# CW308T_CC2538_UFO.net
KiCad netlist of a schematic drawn in Altium Designer
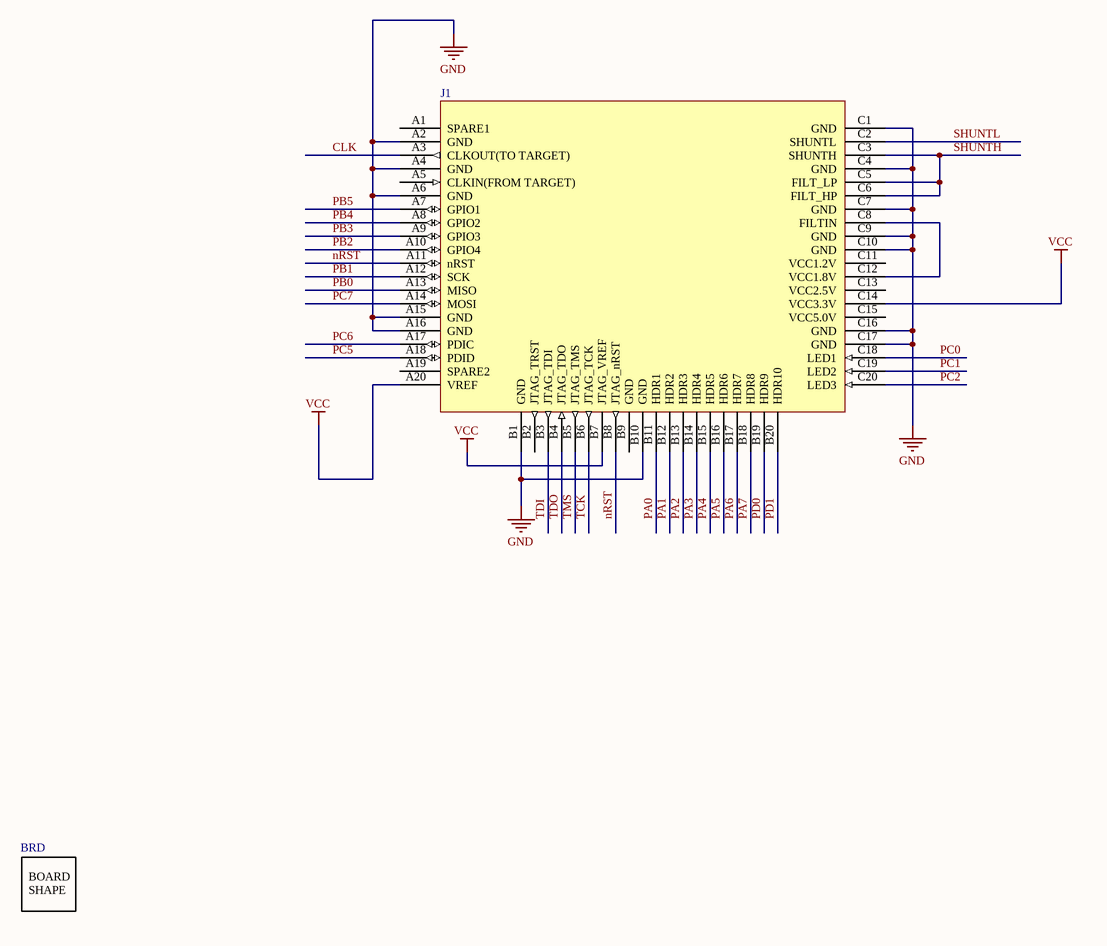
[diagram p0: CW308T_CC2538_UFO.SchDoc]

(export (version "E")
  (design (tool "Eeschema 10.0.6"))
  (components
    (comp (ref "BRD")
      (value "~")
      (footprint "CW308T_TBOARD_DEFSIZE")
      (description "308T Board Outline (Layer 1)")
      (fields (field (name "PART NUMBER") "CW308T_BRDSHAPE_DEFAULT"))
      (libsource (lib "NewAE_AltiumLib") (part "CW308_TBRDSIZE"))
    )
    (comp (ref "J1")
      (value "~")
      (footprint "CW308_TBOARD_CONN")
      (description "CW308 \"Standard\" Target Board Connector")
      (fields (field (name "PART NUMBER") "CW308_TBOARD"))
      (libsource (lib "NewAE_AltiumLib") (part "CW308_TBOARD"))
    )
  )
  (nets
    (net (code "1") (name "/CLK") (class "Default")
      (node (ref "J1") (pin "A3") (pinfunction "CLKOUT(TO_TARGET)_A3") (pintype "output"))
    )
    (net (code "2") (name "/PA0") (class "Default")
      (node (ref "J1") (pin "B11") (pinfunction "HDR1_B11") (pintype "passive"))
    )
    (net (code "3") (name "/PA1") (class "Default")
      (node (ref "J1") (pin "B12") (pinfunction "HDR2_B12") (pintype "passive"))
    )
    (net (code "4") (name "/PA2") (class "Default")
      (node (ref "J1") (pin "B13") (pinfunction "HDR3_B13") (pintype "passive"))
    )
    (net (code "5") (name "/PA3") (class "Default")
      (node (ref "J1") (pin "B14") (pinfunction "HDR4_B14") (pintype "passive"))
    )
    (net (code "6") (name "/PA4") (class "Default")
      (node (ref "J1") (pin "B15") (pinfunction "HDR5_B15") (pintype "passive"))
    )
    (net (code "7") (name "/PA5") (class "Default")
      (node (ref "J1") (pin "B16") (pinfunction "HDR6_B16") (pintype "passive"))
    )
    (net (code "8") (name "/PA6") (class "Default")
      (node (ref "J1") (pin "B17") (pinfunction "HDR7_B17") (pintype "passive"))
    )
    (net (code "9") (name "/PA7") (class "Default")
      (node (ref "J1") (pin "B18") (pinfunction "HDR8_B18") (pintype "passive"))
    )
    (net (code "10") (name "/PB0") (class "Default")
      (node (ref "J1") (pin "A13") (pinfunction "MISO_A13") (pintype "bidirectional"))
    )
    (net (code "11") (name "/PB1") (class "Default")
      (node (ref "J1") (pin "A12") (pinfunction "SCK_A12") (pintype "bidirectional"))
    )
    (net (code "12") (name "/PB2") (class "Default")
      (node (ref "J1") (pin "A10") (pinfunction "GPIO4_A10") (pintype "bidirectional"))
    )
    (net (code "13") (name "/PB3") (class "Default")
      (node (ref "J1") (pin "A9") (pinfunction "GPIO3_A9") (pintype "bidirectional"))
    )
    (net (code "14") (name "/PB4") (class "Default")
      (node (ref "J1") (pin "A8") (pinfunction "GPIO2_A8") (pintype "bidirectional"))
    )
    (net (code "15") (name "/PB5") (class "Default")
      (node (ref "J1") (pin "A7") (pinfunction "GPIO1_A7") (pintype "bidirectional"))
    )
    (net (code "16") (name "/PC0") (class "Default")
      (node (ref "J1") (pin "C18") (pinfunction "LED1_C18") (pintype "input"))
    )
    (net (code "17") (name "/PC1") (class "Default")
      (node (ref "J1") (pin "C19") (pinfunction "LED2_C19") (pintype "input"))
    )
    (net (code "18") (name "/PC2") (class "Default")
      (node (ref "J1") (pin "C20") (pinfunction "LED3_C20") (pintype "input"))
    )
    (net (code "19") (name "/PC5") (class "Default")
      (node (ref "J1") (pin "A18") (pinfunction "PDID_A18") (pintype "bidirectional"))
    )
    (net (code "20") (name "/PC6") (class "Default")
      (node (ref "J1") (pin "A17") (pinfunction "PDIC_A17") (pintype "bidirectional"))
    )
    (net (code "21") (name "/PC7") (class "Default")
      (node (ref "J1") (pin "A14") (pinfunction "MOSI_A14") (pintype "bidirectional"))
    )
    (net (code "22") (name "/PD0") (class "Default")
      (node (ref "J1") (pin "B19") (pinfunction "HDR9_B19") (pintype "passive"))
    )
    (net (code "23") (name "/PD1") (class "Default")
      (node (ref "J1") (pin "B20") (pinfunction "HDR10_B20") (pintype "passive"))
    )
    (net (code "24") (name "/SHUNTH") (class "Default")
      (node (ref "J1") (pin "C3") (pinfunction "SHUNTH_C3") (pintype "passive"))
      (node (ref "J1") (pin "C5") (pinfunction "FILT_LP_C5") (pintype "passive"))
      (node (ref "J1") (pin "C6") (pinfunction "FILT_HP_C6") (pintype "passive"))
    )
    (net (code "25") (name "/SHUNTL") (class "Default")
      (node (ref "J1") (pin "C2") (pinfunction "SHUNTL_C2") (pintype "passive"))
    )
    (net (code "26") (name "/TCK") (class "Default")
      (node (ref "J1") (pin "B6") (pinfunction "JTAG_TCK_B6") (pintype "output"))
    )
    (net (code "27") (name "/TDI") (class "Default")
      (node (ref "J1") (pin "B3") (pinfunction "JTAG_TDI_B3") (pintype "output"))
    )
    (net (code "28") (name "/TDO") (class "Default")
      (node (ref "J1") (pin "B4") (pinfunction "JTAG_TDO_B4") (pintype "input"))
    )
    (net (code "29") (name "/TMS") (class "Default")
      (node (ref "J1") (pin "B5") (pinfunction "JTAG_TMS_B5") (pintype "output"))
    )
    (net (code "30") (name "/nRST") (class "Default")
      (node (ref "J1") (pin "A11") (pinfunction "nRST_A11") (pintype "bidirectional"))
      (node (ref "J1") (pin "B8") (pinfunction "JTAG_nRST_B8") (pintype "output"))
    )
    (net (code "31") (name "GND") (class "Default")
      (node (ref "J1") (pin "A15") (pinfunction "GND_A15") (pintype "passive"))
      (node (ref "J1") (pin "A16") (pinfunction "GND_A16") (pintype "passive"))
      (node (ref "J1") (pin "A2") (pinfunction "GND_A2") (pintype "passive"))
      (node (ref "J1") (pin "A4") (pinfunction "GND_A4") (pintype "passive"))
      (node (ref "J1") (pin "A6") (pinfunction "GND_A6") (pintype "power_in"))
      (node (ref "J1") (pin "B1") (pinfunction "GND_B1") (pintype "passive"))
      (node (ref "J1") (pin "B10") (pinfunction "GND_B10") (pintype "passive"))
      (node (ref "J1") (pin "C1") (pinfunction "GND_C1") (pintype "power_in"))
      (node (ref "J1") (pin "C10") (pinfunction "GND_C10") (pintype "power_in"))
      (node (ref "J1") (pin "C16") (pinfunction "GND_C16") (pintype "power_in"))
      (node (ref "J1") (pin "C17") (pinfunction "GND_C17") (pintype "power_in"))
      (node (ref "J1") (pin "C4") (pinfunction "GND_C4") (pintype "power_in"))
      (node (ref "J1") (pin "C7") (pinfunction "GND_C7") (pintype "power_in"))
      (node (ref "J1") (pin "C9") (pinfunction "GND_C9") (pintype "power_in"))
    )
    (net (code "32") (name "Net-(J1-FILTIN)") (class "Default")
      (node (ref "J1") (pin "C12") (pinfunction "VCC1.8V_C12") (pintype "power_in"))
      (node (ref "J1") (pin "C8") (pinfunction "FILTIN_C8") (pintype "passive"))
    )
    (net (code "33") (name "VCC") (class "Default")
      (node (ref "J1") (pin "A20") (pinfunction "VREF_A20") (pintype "tri_state"))
      (node (ref "J1") (pin "B7") (pinfunction "JTAG_VREF_B7") (pintype "tri_state"))
      (node (ref "J1") (pin "C14") (pinfunction "VCC3.3V_C14") (pintype "power_in"))
    )
    (net (code "34") (name "unconnected-(J1-CLKIN(FROM_TARGET)-PadA5)") (class "Default")
      (node (ref "J1") (pin "A5") (pinfunction "CLKIN(FROM_TARGET)_A5") (pintype "input"))
    )
    (net (code "35") (name "unconnected-(J1-GND-PadB9)") (class "Default")
      (node (ref "J1") (pin "B9") (pinfunction "GND_B9") (pintype "passive"))
    )
    (net (code "36") (name "unconnected-(J1-JTAG_TRST-PadB2)") (class "Default")
      (node (ref "J1") (pin "B2") (pinfunction "JTAG_TRST_B2") (pintype "output"))
    )
    (net (code "37") (name "unconnected-(J1-SPARE1-PadA1)") (class "Default")
      (node (ref "J1") (pin "A1") (pinfunction "SPARE1_A1") (pintype "passive"))
    )
    (net (code "38") (name "unconnected-(J1-SPARE2-PadA19)") (class "Default")
      (node (ref "J1") (pin "A19") (pinfunction "SPARE2_A19") (pintype "passive"))
    )
    (net (code "39") (name "unconnected-(J1-VCC1.2V-PadC11)") (class "Default")
      (node (ref "J1") (pin "C11") (pinfunction "VCC1.2V_C11") (pintype "power_in"))
    )
    (net (code "40") (name "unconnected-(J1-VCC2.5V-PadC13)") (class "Default")
      (node (ref "J1") (pin "C13") (pinfunction "VCC2.5V_C13") (pintype "power_in"))
    )
    (net (code "41") (name "unconnected-(J1-VCC5.0V-PadC15)") (class "Default")
      (node (ref "J1") (pin "C15") (pinfunction "VCC5.0V_C15") (pintype "power_in"))
    )
  )
)
